# mymote-power.net
KiCad netlist of a schematic drawn in EAGLE
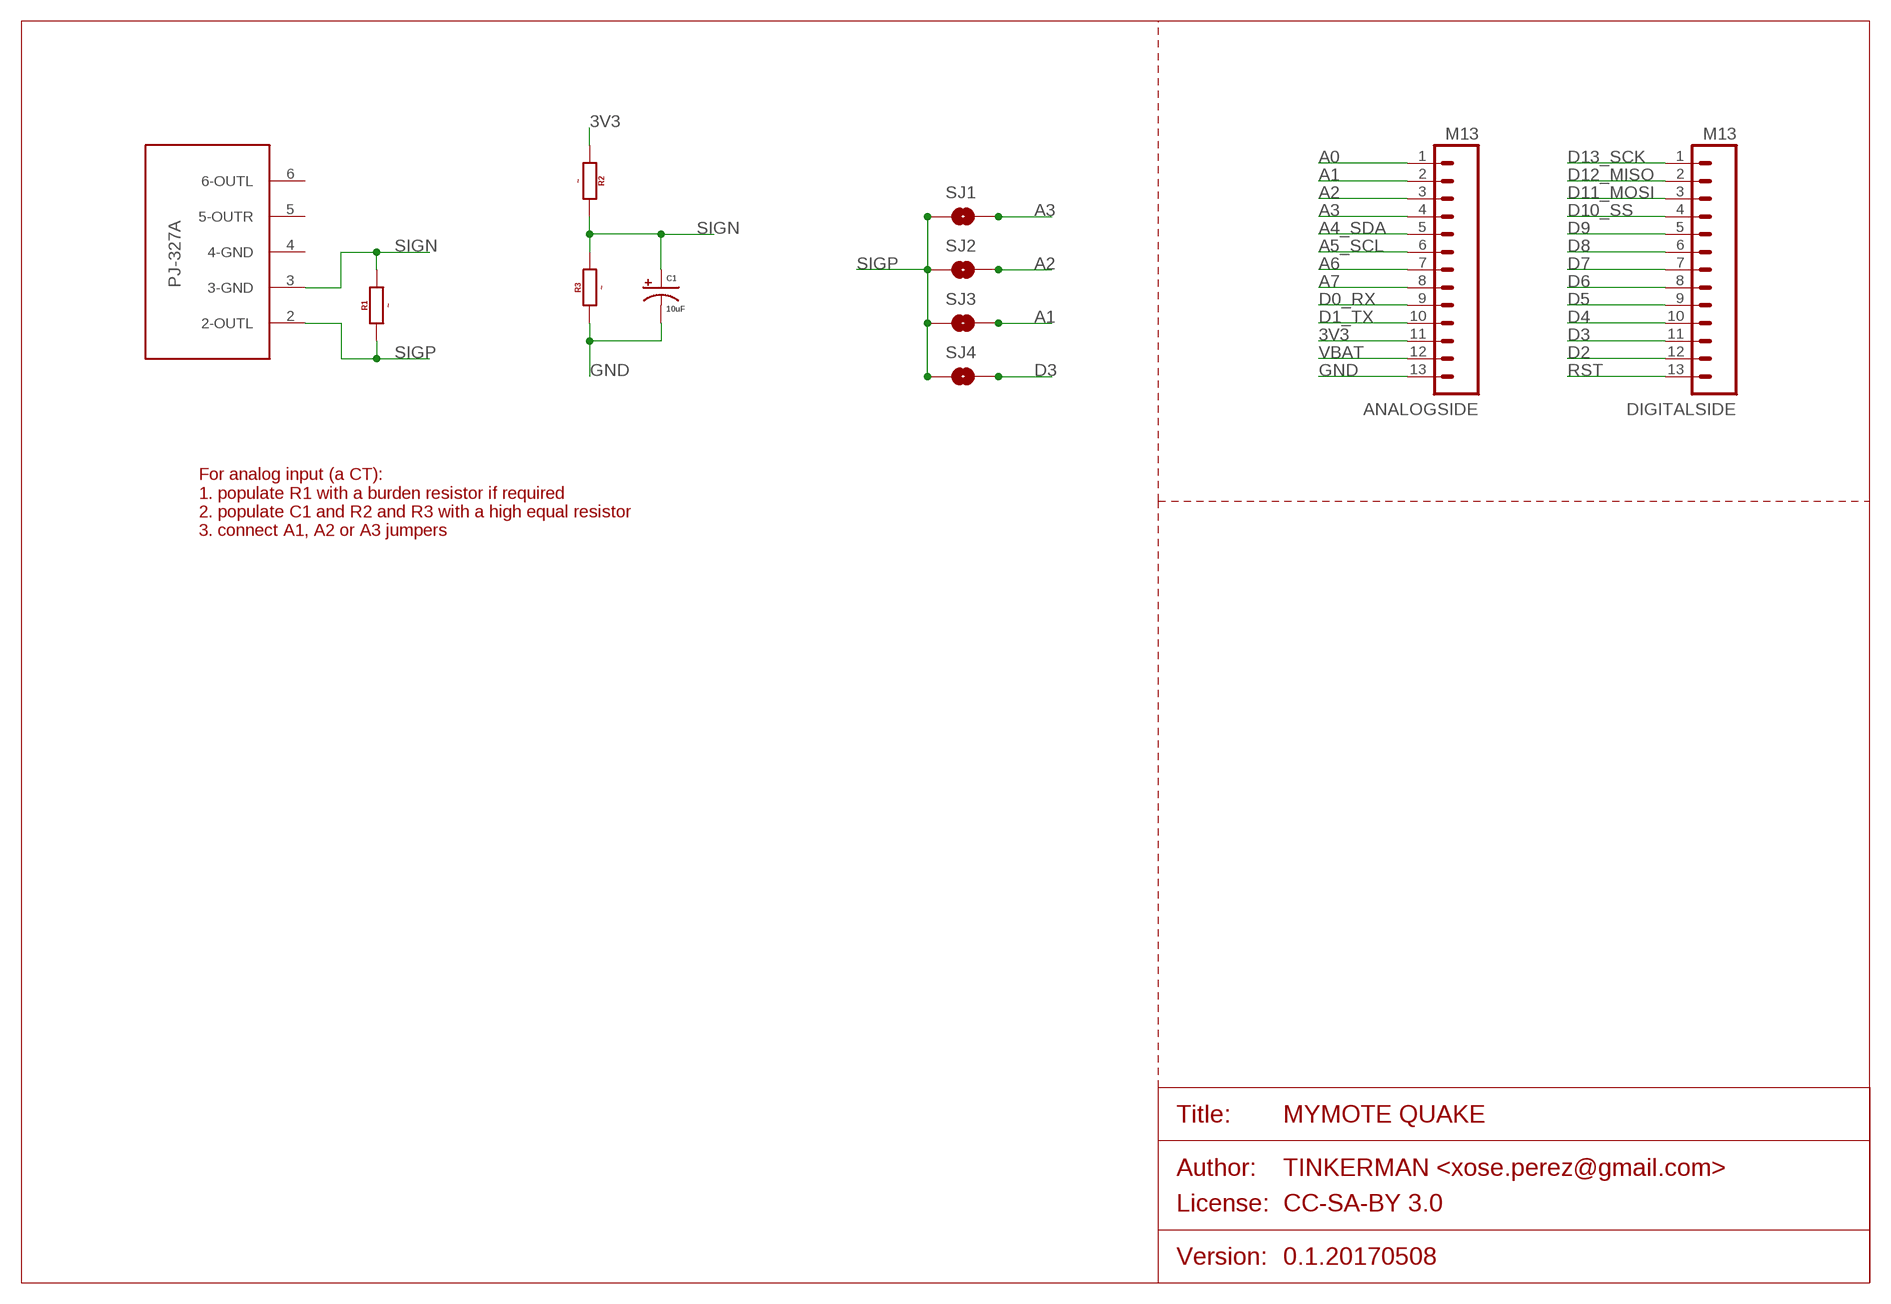
[diagram p0: schematic, sheet 1]

(export (version "E")
  (design (tool "Eeschema 10.0.6"))
  (components
    (comp (ref "ANALOGSIDE")
      (value "M13")
      (footprint "eagle-import:1X13_NO_SILK")
      (libsource (lib "eagle-import") (part "M13"))
    )
    (comp (ref "C1")
      (value "10uF")
      (footprint "eagle-import:PANASONIC_C")
      (libsource (lib "eagle-import") (part "CAP_POLC"))
    )
    (comp (ref "CURR1")
      (value "PJ-327A")
      (footprint "eagle-import:PJ-327A")
      (libsource (lib "eagle-import") (part "PJ-327A"))
    )
    (comp (ref "DIGITALSIDE")
      (value "M13")
      (footprint "eagle-import:1X13_NO_SILK")
      (libsource (lib "eagle-import") (part "M13"))
    )
    (comp (ref "R1")
      (value "~")
      (footprint "eagle-import:0805")
      (libsource (lib "eagle-import") (part "RESISTOR0805"))
    )
    (comp (ref "R2")
      (value "~")
      (footprint "eagle-import:0805")
      (libsource (lib "eagle-import") (part "RESISTOR0805"))
    )
    (comp (ref "R3")
      (value "~")
      (footprint "eagle-import:0805")
      (libsource (lib "eagle-import") (part "RESISTOR0805"))
    )
    (comp (ref "SJ1")
      (value "SOLDERJUMPERNO")
      (footprint "eagle-import:SJ_2S-NO")
      (libsource (lib "eagle-import") (part "SOLDERJUMPERNO"))
    )
    (comp (ref "SJ2")
      (value "SOLDERJUMPERNO")
      (footprint "eagle-import:SJ_2S-NO")
      (libsource (lib "eagle-import") (part "SOLDERJUMPERNO"))
    )
    (comp (ref "SJ3")
      (value "SOLDERJUMPERNO")
      (footprint "eagle-import:SJ_2S-NO")
      (libsource (lib "eagle-import") (part "SOLDERJUMPERNO"))
    )
    (comp (ref "SJ4")
      (value "SOLDERJUMPERNO")
      (footprint "eagle-import:SJ_2S-NO")
      (libsource (lib "eagle-import") (part "SOLDERJUMPERNO"))
    )
  )
  (nets
    (net (code "1") (name "/3V3") (class "Default")
      (node (ref "ANALOGSIDE") (pin "11") (pinfunction "11_11") (pintype "passive"))
      (node (ref "R2") (pin "1") (pinfunction "1_1") (pintype "passive"))
    )
    (net (code "2") (name "/A0") (class "Default")
      (node (ref "ANALOGSIDE") (pin "1") (pinfunction "1_1") (pintype "passive"))
    )
    (net (code "3") (name "/A1") (class "Default")
      (node (ref "ANALOGSIDE") (pin "2") (pinfunction "2_2") (pintype "passive"))
      (node (ref "SJ3") (pin "2") (pinfunction "2_2") (pintype "passive"))
    )
    (net (code "4") (name "/A2") (class "Default")
      (node (ref "ANALOGSIDE") (pin "3") (pinfunction "3_3") (pintype "passive"))
      (node (ref "SJ2") (pin "2") (pinfunction "2_2") (pintype "passive"))
    )
    (net (code "5") (name "/A3") (class "Default")
      (node (ref "ANALOGSIDE") (pin "4") (pinfunction "4_4") (pintype "passive"))
      (node (ref "SJ1") (pin "2") (pinfunction "2_2") (pintype "passive"))
    )
    (net (code "6") (name "/A4_SDA") (class "Default")
      (node (ref "ANALOGSIDE") (pin "5") (pinfunction "5_5") (pintype "passive"))
    )
    (net (code "7") (name "/A5_SCL") (class "Default")
      (node (ref "ANALOGSIDE") (pin "6") (pinfunction "6_6") (pintype "passive"))
    )
    (net (code "8") (name "/A6") (class "Default")
      (node (ref "ANALOGSIDE") (pin "7") (pinfunction "7_7") (pintype "passive"))
    )
    (net (code "9") (name "/A7") (class "Default")
      (node (ref "ANALOGSIDE") (pin "8") (pinfunction "8_8") (pintype "passive"))
    )
    (net (code "10") (name "/D0_RX") (class "Default")
      (node (ref "ANALOGSIDE") (pin "9") (pinfunction "9_9") (pintype "passive"))
    )
    (net (code "11") (name "/D1_TX") (class "Default")
      (node (ref "ANALOGSIDE") (pin "10") (pinfunction "10_10") (pintype "passive"))
    )
    (net (code "12") (name "/D2") (class "Default")
      (node (ref "DIGITALSIDE") (pin "12") (pinfunction "12_12") (pintype "passive"))
    )
    (net (code "13") (name "/D3") (class "Default")
      (node (ref "DIGITALSIDE") (pin "11") (pinfunction "11_11") (pintype "passive"))
      (node (ref "SJ4") (pin "2") (pinfunction "2_2") (pintype "passive"))
    )
    (net (code "14") (name "/D4") (class "Default")
      (node (ref "DIGITALSIDE") (pin "10") (pinfunction "10_10") (pintype "passive"))
    )
    (net (code "15") (name "/D5") (class "Default")
      (node (ref "DIGITALSIDE") (pin "9") (pinfunction "9_9") (pintype "passive"))
    )
    (net (code "16") (name "/D6") (class "Default")
      (node (ref "DIGITALSIDE") (pin "8") (pinfunction "8_8") (pintype "passive"))
    )
    (net (code "17") (name "/D7") (class "Default")
      (node (ref "DIGITALSIDE") (pin "7") (pinfunction "7_7") (pintype "passive"))
    )
    (net (code "18") (name "/D8") (class "Default")
      (node (ref "DIGITALSIDE") (pin "6") (pinfunction "6_6") (pintype "passive"))
    )
    (net (code "19") (name "/D9") (class "Default")
      (node (ref "DIGITALSIDE") (pin "5") (pinfunction "5_5") (pintype "passive"))
    )
    (net (code "20") (name "/D10_SS") (class "Default")
      (node (ref "DIGITALSIDE") (pin "4") (pinfunction "4_4") (pintype "passive"))
    )
    (net (code "21") (name "/D11_MOSI") (class "Default")
      (node (ref "DIGITALSIDE") (pin "3") (pinfunction "3_3") (pintype "passive"))
    )
    (net (code "22") (name "/D12_MISO") (class "Default")
      (node (ref "DIGITALSIDE") (pin "2") (pinfunction "2_2") (pintype "passive"))
    )
    (net (code "23") (name "/D13_SCK") (class "Default")
      (node (ref "DIGITALSIDE") (pin "1") (pinfunction "1_1") (pintype "passive"))
    )
    (net (code "24") (name "/GND") (class "Default")
      (node (ref "ANALOGSIDE") (pin "13") (pinfunction "13_13") (pintype "passive"))
      (node (ref "C1") (pin "-") (pinfunction "-_-") (pintype "passive"))
      (node (ref "R3") (pin "1") (pinfunction "1_1") (pintype "passive"))
    )
    (net (code "25") (name "/RST") (class "Default")
      (node (ref "DIGITALSIDE") (pin "13") (pinfunction "13_13") (pintype "passive"))
    )
    (net (code "26") (name "/SIGN") (class "Default")
      (node (ref "C1") (pin "+") (pinfunction "+_+") (pintype "passive"))
      (node (ref "CURR1") (pin "3") (pinfunction "3-GND_3") (pintype "bidirectional"))
      (node (ref "R1") (pin "2") (pinfunction "2_2") (pintype "passive"))
      (node (ref "R2") (pin "2") (pinfunction "2_2") (pintype "passive"))
      (node (ref "R3") (pin "2") (pinfunction "2_2") (pintype "passive"))
    )
    (net (code "27") (name "/SIGP") (class "Default")
      (node (ref "CURR1") (pin "2") (pinfunction "2-OUTL_2") (pintype "bidirectional"))
      (node (ref "R1") (pin "1") (pinfunction "1_1") (pintype "passive"))
      (node (ref "SJ1") (pin "1") (pinfunction "1_1") (pintype "passive"))
      (node (ref "SJ2") (pin "1") (pinfunction "1_1") (pintype "passive"))
      (node (ref "SJ3") (pin "1") (pinfunction "1_1") (pintype "passive"))
      (node (ref "SJ4") (pin "1") (pinfunction "1_1") (pintype "passive"))
    )
    (net (code "28") (name "/VBAT") (class "Default")
      (node (ref "ANALOGSIDE") (pin "12") (pinfunction "12_12") (pintype "passive"))
    )
    (net (code "29") (name "unconnected-(CURR1-4-GND-Pad4)") (class "Default")
      (node (ref "CURR1") (pin "4") (pinfunction "4-GND_4") (pintype "bidirectional"))
    )
    (net (code "30") (name "unconnected-(CURR1-5-OUTR-Pad5)") (class "Default")
      (node (ref "CURR1") (pin "5") (pinfunction "5-OUTR_5") (pintype "bidirectional"))
    )
    (net (code "31") (name "unconnected-(CURR1-6-OUTL-Pad6)") (class "Default")
      (node (ref "CURR1") (pin "6") (pinfunction "6-OUTL_6") (pintype "bidirectional"))
    )
  )
)
